# mv-uart.net
KiCad netlist of a schematic drawn in EAGLE
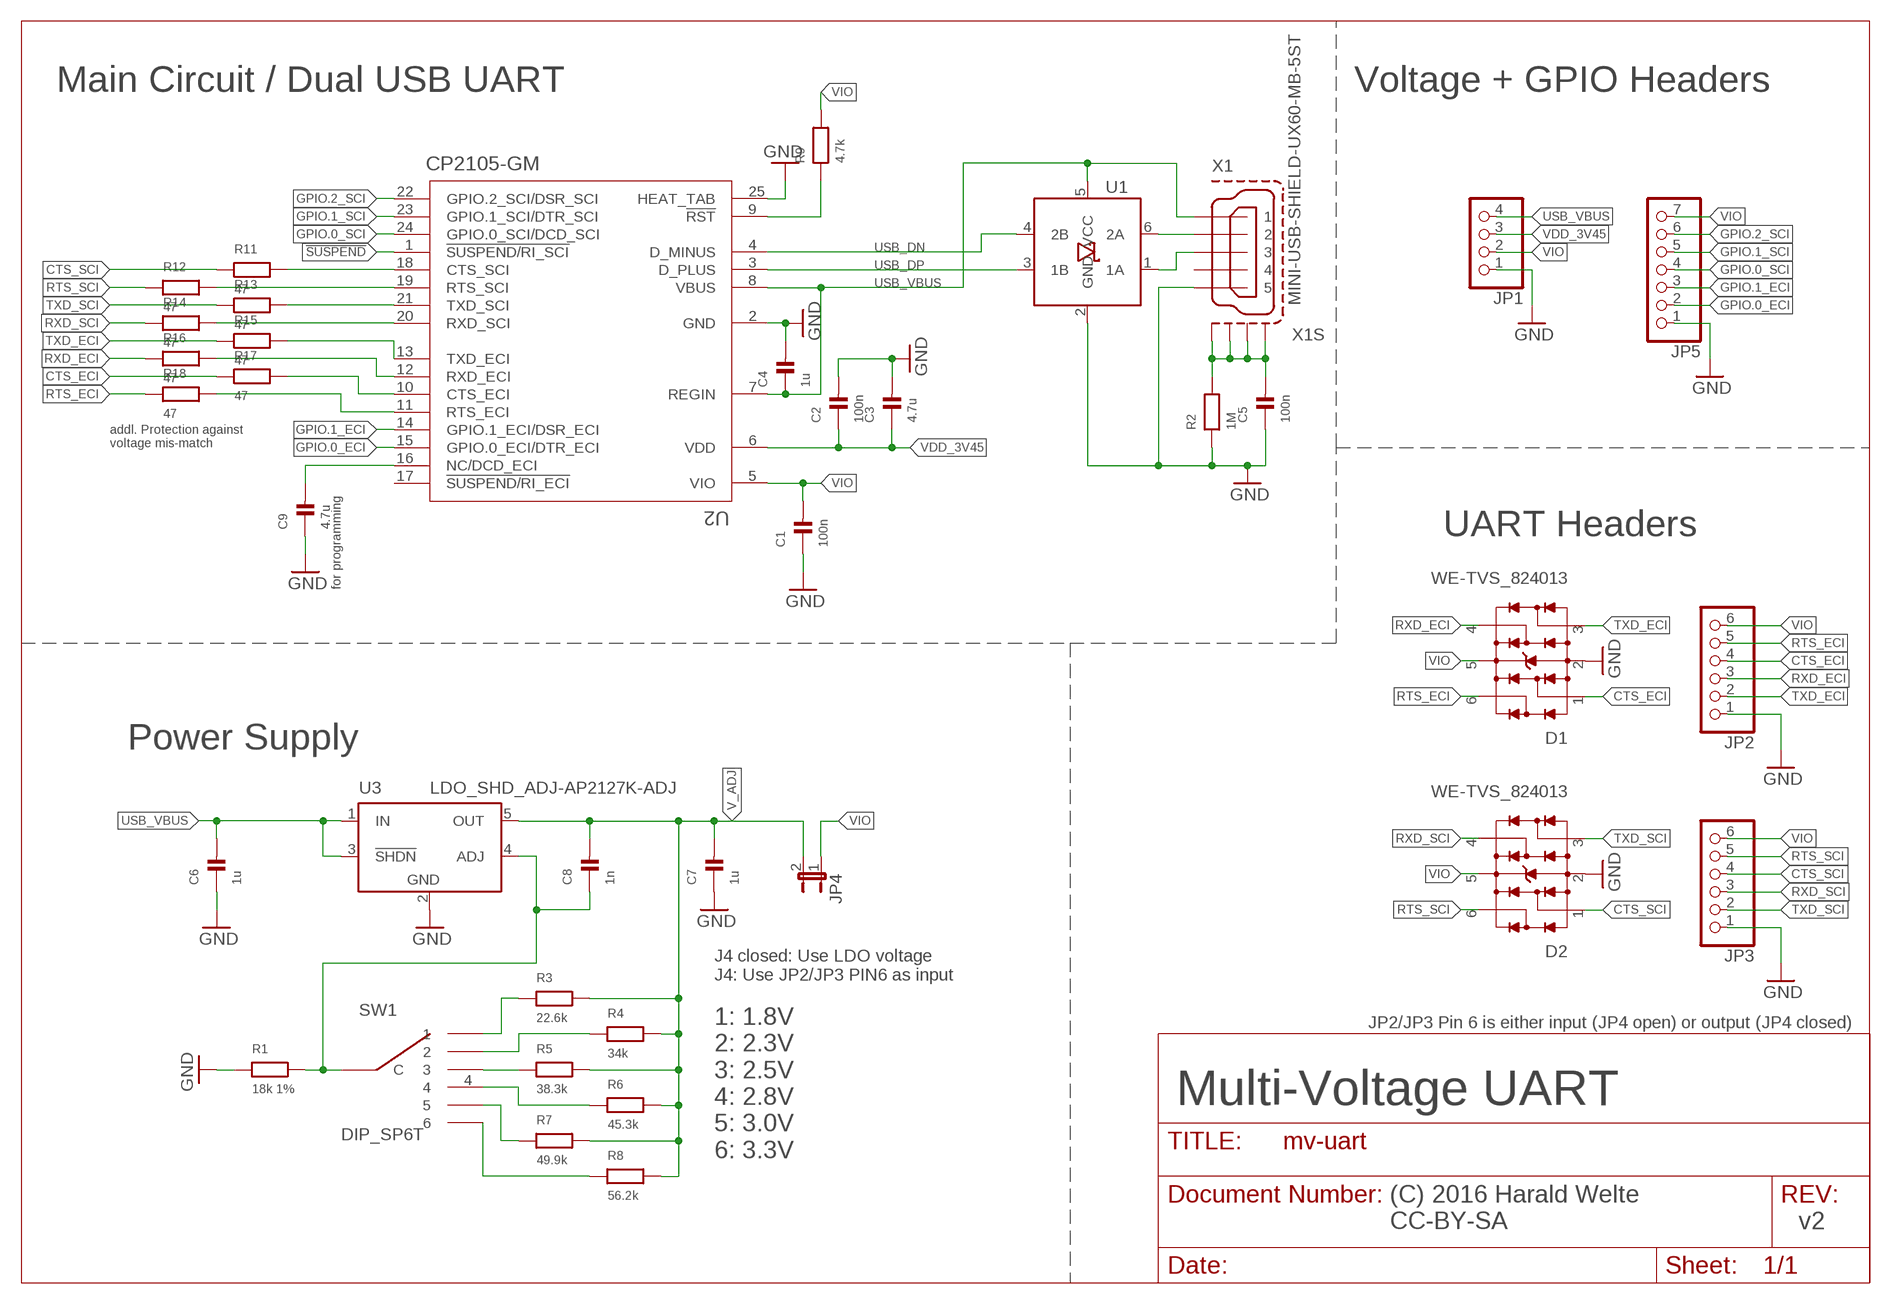
[diagram p0: schematic, sheet 1]

(export (version "E")
  (design (tool "Eeschema 10.0.6"))
  (components
    (comp (ref "C1")
      (value "100n")
      (footprint "eagle-import:_0603")
      (description "0.10µF 16V Ceramic Capacitor X5R 0201 (0603 Metric) 0.024\" L x 0.012\" W (0.60mm x 0.30mm)")
      (fields
        (field (name "MANUFACTURER") "Murata Electronics North America")
        (field (name "MANUFACTURERPARTNUMBER") "GRM033R61C104KE84D")
      )
      (libsource (lib "eagle-import") (part "CAP_CERAMIC_0603"))
    )
    (comp (ref "C2")
      (value "100n")
      (footprint "eagle-import:_0603")
      (description "0.10µF 16V Ceramic Capacitor X5R 0201 (0603 Metric) 0.024\" L x 0.012\" W (0.60mm x 0.30mm)")
      (fields
        (field (name "MANUFACTURER") "Murata Electronics North America")
        (field (name "MANUFACTURERPARTNUMBER") "GRM033R61C104KE84D")
      )
      (libsource (lib "eagle-import") (part "CAP_CERAMIC_0603"))
    )
    (comp (ref "C3")
      (value "4.7u")
      (footprint "eagle-import:_0603")
      (description "4.7µF 10V Ceramic Capacitor X5R 0603 (1608 Metric) 0.063\" L x 0.031\" W (1.60mm x 0.80mm)")
      (fields
        (field (name "MANUFACTURER") "Samsung Electro-Mechanics America, Inc.")
        (field (name "MANUFACTURERPARTNUMBER") "CL10A475KP8NNNC")
      )
      (libsource (lib "eagle-import") (part "CAP_CERAMIC_0603"))
    )
    (comp (ref "C4")
      (value "1u")
      (footprint "eagle-import:_0603")
      (description "1µF 16V Ceramic Capacitor X5R 0603 (1608 Metric) 0.063\" L x 0.031\" W (1.60mm x 0.80mm)")
      (fields
        (field (name "MANUFACTURER") "Murata Electronics North America")
        (field (name "MANUFACTURERPARTNUMBER") "GRM188R61C105KA93J")
      )
      (libsource (lib "eagle-import") (part "CAP_CERAMIC_0603"))
    )
    (comp (ref "C5")
      (value "100n")
      (footprint "eagle-import:_0603")
      (description "0.10µF 16V Ceramic Capacitor X5R 0201 (0603 Metric) 0.024\" L x 0.012\" W (0.60mm x 0.30mm)")
      (fields
        (field (name "MANUFACTURER") "Murata Electronics North America")
        (field (name "MANUFACTURERPARTNUMBER") "GRM033R61C104KE84D")
      )
      (libsource (lib "eagle-import") (part "CAP_CERAMIC_0603"))
    )
    (comp (ref "C6")
      (value "1u")
      (footprint "eagle-import:_0603")
      (description "1µF 16V Ceramic Capacitor X5R 0603 (1608 Metric) 0.063\" L x 0.031\" W (1.60mm x 0.80mm)")
      (fields
        (field (name "MANUFACTURER") "Murata Electronics North America")
        (field (name "MANUFACTURERPARTNUMBER") "GRM188R61C105KA93J")
      )
      (libsource (lib "eagle-import") (part "CAP_CERAMIC_0603"))
    )
    (comp (ref "C7")
      (value "1u")
      (footprint "eagle-import:_0603")
      (description "1µF 16V Ceramic Capacitor X5R 0603 (1608 Metric) 0.063\" L x 0.031\" W (1.60mm x 0.80mm)")
      (fields
        (field (name "MANUFACTURER") "Murata Electronics North America")
        (field (name "MANUFACTURERPARTNUMBER") "GRM188R61C105KA93J")
      )
      (libsource (lib "eagle-import") (part "CAP_CERAMIC_0603"))
    )
    (comp (ref "C8")
      (value "1n")
      (footprint "eagle-import:_0603")
      (description "1000pF 100V Ceramic Capacitor X7R 0603 (1608 Metric) 0.063\" L x 0.031\" W (1.60mm x 0.80mm)")
      (fields
        (field (name "MANUFACTURER") "Samsung Electro-Mechanics America, Inc.")
        (field (name "MANUFACTURERPARTNUMBER") "CL10B102KC8NNNC")
      )
      (libsource (lib "eagle-import") (part "CAP_CERAMIC_0603"))
    )
    (comp (ref "C9")
      (value "4.7u")
      (footprint "eagle-import:_0603")
      (description "4.7µF 10V Ceramic Capacitor X5R 0603 (1608 Metric) 0.063\" L x 0.031\" W (1.60mm x 0.80mm)")
      (fields
        (field (name "MANUFACTURER") "Samsung Electro-Mechanics America, Inc.")
        (field (name "MANUFACTURERPARTNUMBER") "CL10A475KP8NNNC")
      )
      (libsource (lib "eagle-import") (part "CAP_CERAMIC_0603"))
    )
    (comp (ref "D1")
      (value "WE-TVS_824013")
      (footprint "eagle-import:WE-TVS_SOT23-6L")
      (description "TVS DIODE 3.3VWM 6VC SOT23")
      (fields
        (field (name "MANUFACTURER") "Wurth Electronics Inc")
        (field (name "MANUFACTURERPARTNUMBER") "824013")
      )
      (libsource (lib "eagle-import") (part "WE-TVS_824013"))
    )
    (comp (ref "D2")
      (value "WE-TVS_824013")
      (footprint "eagle-import:WE-TVS_SOT23-6L")
      (description "TVS DIODE 3.3VWM 6VC SOT23")
      (fields
        (field (name "MANUFACTURER") "Wurth Electronics Inc")
        (field (name "MANUFACTURERPARTNUMBER") "824013")
      )
      (libsource (lib "eagle-import") (part "WE-TVS_824013"))
    )
    (comp (ref "JP1")
      (value "PINHD-1X4")
      (footprint "eagle-import:1X04")
      (description "4 Positions Header, Unshrouded, Breakaway Connector 0.100\" (2.54mm) Through Hole Gold")
      (fields
        (field (name "MANUFACTURER") "Harwin Inc.")
        (field (name "MANUFACTURERPARTNUMBER") "M20-9990445")
      )
      (libsource (lib "eagle-import") (part "PINHD-1X4"))
    )
    (comp (ref "JP2")
      (value "PINHD-1X6/90")
      (footprint "eagle-import:1X06_90")
      (fields
        (field (name "MANUFACTURER") "Harwin Inc.")
        (field (name "MANUFACTURERPARTNUMBER") "M20-9960645")
      )
      (libsource (lib "eagle-import") (part "PINHD-1X6/90"))
    )
    (comp (ref "JP3")
      (value "PINHD-1X6/90")
      (footprint "eagle-import:1X06_90")
      (fields
        (field (name "MANUFACTURER") "Harwin Inc.")
        (field (name "MANUFACTURERPARTNUMBER") "M20-9960645")
      )
      (libsource (lib "eagle-import") (part "PINHD-1X6/90"))
    )
    (comp (ref "JP4")
      (value "JP1E")
      (footprint "eagle-import:JP1")
      (description "NO DESCRIPTION")
      (fields
        (field (name "MANUFACTURER") "UNKNOWN MANUFACTURER")
        (field (name "MANUFACTURERPARTNUMBER") "UNKNOWN MANUFACTURER PART NUMBER")
      )
      (libsource (lib "eagle-import") (part "JP1E"))
    )
    (comp (ref "JP5")
      (value "PINHD-1X7")
      (footprint "eagle-import:1X07")
      (description "7 Positions Header, Unshrouded, Breakaway Connector 0.100\" (2.54mm) Through Hole Gold")
      (fields
        (field (name "MANUFACTURER") "Sullins Connector Solutions")
        (field (name "MANUFACTURERPARTNUMBER") "PRPC007SAAN-RC")
      )
      (libsource (lib "eagle-import") (part "PINHD-1X7"))
    )
    (comp (ref "R1")
      (value "18k 1%")
      (footprint "eagle-import:_0603")
      (description "RES SMD 18K OHM 1% 1/10W 0603")
      (fields (field (name "MANUFACTURER") "Yageo") (field (name "MANUFACTURERPARTNUMBER") "RC0603FR-0718KL"))
      (libsource (lib "eagle-import") (part "RESISTOR_0603"))
    )
    (comp (ref "R2")
      (value "1M")
      (footprint "eagle-import:_0603")
      (description "RES SMD 1M OHM 5% 1/20W 0201")
      (fields
        (field (name "MANUFACTURER") "Samsung Electro-Mechanics America, Inc.")
        (field (name "MANUFACTURERPARTNUMBER") "RC0603J105CS")
      )
      (libsource (lib "eagle-import") (part "RESISTOR_0603"))
    )
    (comp (ref "R3")
      (value "22.6k")
      (footprint "eagle-import:_0603")
      (description "RES SMD 22.6K OHM 1% 1/10W 0603")
      (fields
        (field (name "MANUFACTURER") "Yageo")
        (field (name "MANUFACTURERPARTNUMBER") "RC0603FR-0722K6L")
      )
      (libsource (lib "eagle-import") (part "RESISTOR_0603"))
    )
    (comp (ref "R4")
      (value "34k")
      (footprint "eagle-import:_0603")
      (description "RES SMD 34K OHM 1% 1/10W 0603")
      (fields (field (name "MANUFACTURER") "Yageo") (field (name "MANUFACTURERPARTNUMBER") "RC0603FR-0734KL"))
      (libsource (lib "eagle-import") (part "RESISTOR_0603"))
    )
    (comp (ref "R5")
      (value "38.3k")
      (footprint "eagle-import:_0603")
      (description "RES SMD 38.3K OHM 1% 1/10W 0603")
      (fields
        (field (name "MANUFACTURER") "Yageo")
        (field (name "MANUFACTURERPARTNUMBER") "RC0603FR-0738K3L")
      )
      (libsource (lib "eagle-import") (part "RESISTOR_0603"))
    )
    (comp (ref "R6")
      (value "45.3k")
      (footprint "eagle-import:_0603")
      (description "RES SMD 45.3K OHM 1% 1/10W 0603")
      (fields
        (field (name "MANUFACTURER") "Yageo")
        (field (name "MANUFACTURERPARTNUMBER") "RC0603FR-0745K3L")
      )
      (libsource (lib "eagle-import") (part "RESISTOR_0603"))
    )
    (comp (ref "R7")
      (value "49.9k")
      (footprint "eagle-import:_0603")
      (description "RES SMD 49.9K OHM 1% 1/10W 0603")
      (fields
        (field (name "MANUFACTURER") "Yageo")
        (field (name "MANUFACTURERPARTNUMBER") "RC0603FR-0749K9L")
      )
      (libsource (lib "eagle-import") (part "RESISTOR_0603"))
    )
    (comp (ref "R8")
      (value "56.2k")
      (footprint "eagle-import:_0603")
      (description "RES SMD 56.2K OHM 1% 1/10W 0603")
      (fields
        (field (name "MANUFACTURER") "Yageo")
        (field (name "MANUFACTURERPARTNUMBER") "RC0603FR-0756K2L")
      )
      (libsource (lib "eagle-import") (part "RESISTOR_0603"))
    )
    (comp (ref "R9")
      (value "4.7k")
      (footprint "eagle-import:_0603")
      (description "RES SMD 4.7K OHM 5% 1/10W 0603")
      (fields (field (name "MANUFACTURER") "Yageo") (field (name "MANUFACTURERPARTNUMBER") "RC0603JR-074K7L"))
      (libsource (lib "eagle-import") (part "RESISTOR_0603"))
    )
    (comp (ref "R11")
      (value "47")
      (footprint "eagle-import:_0603")
      (description "RES SMD 47 OHM 5% 1/10W 0603")
      (fields (field (name "MANUFACTURER") "Yageo") (field (name "MANUFACTURERPARTNUMBER") "RC0603JR-0747RL"))
      (libsource (lib "eagle-import") (part "RESISTOR_0603"))
    )
    (comp (ref "R12")
      (value "47")
      (footprint "eagle-import:_0603")
      (description "RES SMD 47 OHM 5% 1/10W 0603")
      (fields (field (name "MANUFACTURER") "Yageo") (field (name "MANUFACTURERPARTNUMBER") "RC0603JR-0747RL"))
      (libsource (lib "eagle-import") (part "RESISTOR_0603"))
    )
    (comp (ref "R13")
      (value "47")
      (footprint "eagle-import:_0603")
      (description "RES SMD 47 OHM 5% 1/10W 0603")
      (fields (field (name "MANUFACTURER") "Yageo") (field (name "MANUFACTURERPARTNUMBER") "RC0603JR-0747RL"))
      (libsource (lib "eagle-import") (part "RESISTOR_0603"))
    )
    (comp (ref "R14")
      (value "47")
      (footprint "eagle-import:_0603")
      (description "RES SMD 47 OHM 5% 1/10W 0603")
      (fields (field (name "MANUFACTURER") "Yageo") (field (name "MANUFACTURERPARTNUMBER") "RC0603JR-0747RL"))
      (libsource (lib "eagle-import") (part "RESISTOR_0603"))
    )
    (comp (ref "R15")
      (value "47")
      (footprint "eagle-import:_0603")
      (description "RES SMD 47 OHM 5% 1/10W 0603")
      (fields (field (name "MANUFACTURER") "Yageo") (field (name "MANUFACTURERPARTNUMBER") "RC0603JR-0747RL"))
      (libsource (lib "eagle-import") (part "RESISTOR_0603"))
    )
    (comp (ref "R16")
      (value "47")
      (footprint "eagle-import:_0603")
      (description "RES SMD 47 OHM 5% 1/10W 0603")
      (fields (field (name "MANUFACTURER") "Yageo") (field (name "MANUFACTURERPARTNUMBER") "RC0603JR-0747RL"))
      (libsource (lib "eagle-import") (part "RESISTOR_0603"))
    )
    (comp (ref "R17")
      (value "47")
      (footprint "eagle-import:_0603")
      (description "RES SMD 47 OHM 5% 1/10W 0603")
      (fields (field (name "MANUFACTURER") "Yageo") (field (name "MANUFACTURERPARTNUMBER") "RC0603JR-0747RL"))
      (libsource (lib "eagle-import") (part "RESISTOR_0603"))
    )
    (comp (ref "R18")
      (value "47")
      (footprint "eagle-import:_0603")
      (description "RES SMD 47 OHM 5% 1/10W 0603")
      (fields (field (name "MANUFACTURER") "Yageo") (field (name "MANUFACTURERPARTNUMBER") "RC0603JR-0747RL"))
      (libsource (lib "eagle-import") (part "RESISTOR_0603"))
    )
    (comp (ref "SW1")
      (value "DIP_SP6T")
      (footprint "eagle-import:DIP_SP6T")
      (description "Dip Switch SP6T 6 Position Through Hole Rotary with Shaft Actuator 100mA 5VDC")
      (fields
        (field (name "MANUFACTURER") "Copal Electronics Inc.")
        (field (name "MANUFACTURERPARTNUMBER") "SS-10-16SP-L-AE")
      )
      (libsource (lib "eagle-import") (part "DIP_SP6T"))
    )
    (comp (ref "U1")
      (value "IP4234CZ6")
      (footprint "eagle-import:TSOP-6")
      (description "TVS DIODE 5.5VWM 6TSOP")
      (fields
        (field (name "MANUFACTURER") "NXP Semiconductors")
        (field (name "MANUFACTURERPARTNUMBER") "IP4234CZ6,125")
      )
      (libsource (lib "eagle-import") (part "IP4234CZ6"))
    )
    (comp (ref "U2")
      (value "CP2105-GM")
      (footprint "eagle-import:QFN24_4X4")
      (description "USB Bridge, USB to UART USB 2.0 UART Interface 24-QFN (4x4)")
      (fields
        (field (name "MANUFACTURER") "Silicon Labs")
        (field (name "MANUFACTURERPARTNUMBER") "CP2105-F01-GM")
      )
      (libsource (lib "eagle-import") (part "CP2105-GM"))
    )
    (comp (ref "U3")
      (value "LDO_SHD_ADJ-AP2127K-ADJ")
      (footprint "eagle-import:SOT23L")
      (description "Linear Voltage Regulator IC Positive Adjustable 1 Output 0.8 V ~ 5.5 V 300mA SOT-23-5")
      (fields
        (field (name "MANUFACTURER") "Diodes Incorporated")
        (field (name "MANUFACTURERPARTNUMBER") "AP2127K-ADJTRG1")
      )
      (libsource (lib "eagle-import") (part "LDO_SHD_ADJ-AP2127K-ADJ"))
    )
    (comp (ref "X1")
      (value "MINI-USB-SHIELD-UX60-MB-5ST")
      (footprint "eagle-import:UX60-MB-5ST")
      (description "USB - mini B USB 2.0 Receptacle Connector 5 Position Surface Mount, Right Angle, Horizontal")
      (fields
        (field (name "MANUFACTURER") "Hirose Electric Co Ltd")
        (field (name "MANUFACTURERPARTNUMBER") "UX60-MB-5ST")
        (field (name "CLASS") "CONNECTOR")
        (field (name "LINK") "http://www.digikey.com/product-detail/en/hirose-electric-co-ltd/UX60-MB-5ST/H2959CT-ND/597538")
        (field (name "POPULATED") "TRUE")
        (field (name "ROHSCERTIFICATE") "UNKNOWN ROHS CERTIFICATE")
        (field (name "SOURCE") "DIGIKEY")
        (field (name "SOURCEPARTNUMBER") "H2959CT-ND")
      )
      (libsource (lib "eagle-import") (part "MINI-USB-SHIELD-UX60-MB-5ST"))
    )
  )
  (nets
    (net (code "1") (name "/USB_DN") (class "Default")
      (node (ref "U1") (pin "4") (pinfunction "2B_4") (pintype "passive"))
      (node (ref "U2") (pin "4") (pinfunction "D_MINUS_4") (pintype "passive"))
    )
    (net (code "2") (name "/USB_DP") (class "Default")
      (node (ref "U1") (pin "3") (pinfunction "1B_3") (pintype "passive"))
      (node (ref "U2") (pin "3") (pinfunction "D_PLUS_3") (pintype "passive"))
    )
    (net (code "3") (name "/~{SUSPEND}") (class "Default")
      (node (ref "U2") (pin "1") (pinfunction "~{SUSPEND/RI_SCI}_1") (pintype "passive"))
    )
    (net (code "4") (name "CTS_ECI") (class "Default")
      (node (ref "D1") (pin "1") (pinfunction "1_1") (pintype "passive"))
      (node (ref "JP2") (pin "4") (pinfunction "4_4") (pintype "passive"))
      (node (ref "R17") (pin "1") (pinfunction "1_1") (pintype "passive"))
    )
    (net (code "5") (name "CTS_SCI") (class "Default")
      (node (ref "D2") (pin "1") (pinfunction "1_1") (pintype "passive"))
      (node (ref "JP3") (pin "4") (pinfunction "4_4") (pintype "passive"))
      (node (ref "R11") (pin "1") (pinfunction "1_1") (pintype "passive"))
    )
    (net (code "6") (name "GND") (class "Default")
      (node (ref "C1") (pin "1") (pinfunction "1_1") (pintype "passive"))
      (node (ref "C2") (pin "2") (pinfunction "2_2") (pintype "passive"))
      (node (ref "C3") (pin "2") (pinfunction "2_2") (pintype "passive"))
      (node (ref "C4") (pin "2") (pinfunction "2_2") (pintype "passive"))
      (node (ref "C5") (pin "1") (pinfunction "1_1") (pintype "passive"))
      (node (ref "C6") (pin "1") (pinfunction "1_1") (pintype "passive"))
      (node (ref "C7") (pin "1") (pinfunction "1_1") (pintype "passive"))
      (node (ref "C9") (pin "1") (pinfunction "1_1") (pintype "passive"))
      (node (ref "D1") (pin "2") (pinfunction "GND_2") (pintype "power_in"))
      (node (ref "D2") (pin "2") (pinfunction "GND_2") (pintype "power_in"))
      (node (ref "JP1") (pin "1") (pinfunction "1_1") (pintype "passive"))
      (node (ref "JP2") (pin "1") (pinfunction "1_1") (pintype "passive"))
      (node (ref "JP3") (pin "1") (pinfunction "1_1") (pintype "passive"))
      (node (ref "JP5") (pin "1") (pinfunction "1_1") (pintype "passive"))
      (node (ref "R1") (pin "1") (pinfunction "1_1") (pintype "passive"))
      (node (ref "R2") (pin "1") (pinfunction "1_1") (pintype "passive"))
      (node (ref "U1") (pin "2") (pinfunction "GND_2") (pintype "passive"))
      (node (ref "U2") (pin "2") (pinfunction "GND_2") (pintype "power_in"))
      (node (ref "U2") (pin "25") (pinfunction "HEAT_TAB_25") (pintype "passive"))
      (node (ref "U3") (pin "2") (pinfunction "GND_2") (pintype "power_in"))
      (node (ref "X1") (pin "5") (pinfunction "5_5") (pintype "input"))
    )
    (net (code "7") (name "GPIO.0_ECI") (class "Default")
      (node (ref "JP5") (pin "2") (pinfunction "2_2") (pintype "passive"))
      (node (ref "U2") (pin "15") (pinfunction "GPIO.0_ECI/DTR_ECI_15") (pintype "passive"))
    )
    (net (code "8") (name "GPIO.0_SCI") (class "Default")
      (node (ref "JP5") (pin "4") (pinfunction "4_4") (pintype "passive"))
      (node (ref "U2") (pin "24") (pinfunction "GPIO.0_SCI/DCD_SCI_24") (pintype "passive"))
    )
    (net (code "9") (name "GPIO.1_ECI") (class "Default")
      (node (ref "JP5") (pin "3") (pinfunction "3_3") (pintype "passive"))
      (node (ref "U2") (pin "14") (pinfunction "GPIO.1_ECI/DSR_ECI_14") (pintype "passive"))
    )
    (net (code "10") (name "GPIO.1_SCI") (class "Default")
      (node (ref "JP5") (pin "5") (pinfunction "5_5") (pintype "passive"))
      (node (ref "U2") (pin "23") (pinfunction "GPIO.1_SCI/DTR_SCI_23") (pintype "passive"))
    )
    (net (code "11") (name "GPIO.2_SCI") (class "Default")
      (node (ref "JP5") (pin "6") (pinfunction "6_6") (pintype "passive"))
      (node (ref "U2") (pin "22") (pinfunction "GPIO.2_SCI/DSR_SCI_22") (pintype "passive"))
    )
    (net (code "12") (name "Net-(R3-Pad1)") (class "Default")
      (node (ref "R3") (pin "1") (pinfunction "1_1") (pintype "passive"))
      (node (ref "SW1") (pin "1") (pinfunction "1_1") (pintype "bidirectional"))
    )
    (net (code "13") (name "Net-(R4-Pad1)") (class "Default")
      (node (ref "R4") (pin "1") (pinfunction "1_1") (pintype "passive"))
      (node (ref "SW1") (pin "2") (pinfunction "2_2") (pintype "bidirectional"))
    )
    (net (code "14") (name "Net-(R5-Pad1)") (class "Default")
      (node (ref "R5") (pin "1") (pinfunction "1_1") (pintype "passive"))
      (node (ref "SW1") (pin "3") (pinfunction "3_3") (pintype "bidirectional"))
    )
    (net (code "15") (name "Net-(R6-Pad1)") (class "Default")
      (node (ref "R6") (pin "1") (pinfunction "1_1") (pintype "passive"))
      (node (ref "SW1") (pin "4") (pinfunction "4_4") (pintype "bidirectional"))
    )
    (net (code "16") (name "Net-(R7-Pad1)") (class "Default")
      (node (ref "R7") (pin "1") (pinfunction "1_1") (pintype "passive"))
      (node (ref "SW1") (pin "5") (pinfunction "5_5") (pintype "bidirectional"))
    )
    (net (code "17") (name "Net-(R8-Pad1)") (class "Default")
      (node (ref "R8") (pin "1") (pinfunction "1_1") (pintype "passive"))
      (node (ref "SW1") (pin "6") (pinfunction "6_6") (pintype "bidirectional"))
    )
    (net (code "18") (name "Net-(U1-1A)") (class "Default")
      (node (ref "U1") (pin "1") (pinfunction "1A_1") (pintype "passive"))
      (node (ref "X1") (pin "3") (pinfunction "3_3") (pintype "input"))
    )
    (net (code "19") (name "Net-(U1-2A)") (class "Default")
      (node (ref "U1") (pin "6") (pinfunction "2A_6") (pintype "passive"))
      (node (ref "X1") (pin "2") (pinfunction "2_2") (pintype "input"))
    )
    (net (code "20") (name "Net-(U2-CTS_ECI)") (class "Default")
      (node (ref "R17") (pin "2") (pinfunction "2_2") (pintype "passive"))
      (node (ref "U2") (pin "10") (pinfunction "CTS_ECI_10") (pintype "passive"))
    )
    (net (code "21") (name "Net-(U2-CTS_SCI)") (class "Default")
      (node (ref "R11") (pin "2") (pinfunction "2_2") (pintype "passive"))
      (node (ref "U2") (pin "18") (pinfunction "CTS_SCI_18") (pintype "passive"))
    )
    (net (code "22") (name "Net-(U2-NC{slash}DCD_ECI)") (class "Default")
      (node (ref "C9") (pin "2") (pinfunction "2_2") (pintype "passive"))
      (node (ref "U2") (pin "16") (pinfunction "NC/DCD_ECI_16") (pintype "passive"))
    )
    (net (code "23") (name "Net-(U2-RTS_ECI)") (class "Default")
      (node (ref "R18") (pin "2") (pinfunction "2_2") (pintype "passive"))
      (node (ref "U2") (pin "11") (pinfunction "RTS_ECI_11") (pintype "passive"))
    )
    (net (code "24") (name "Net-(U2-RTS_SCI)") (class "Default")
      (node (ref "R12") (pin "2") (pinfunction "2_2") (pintype "passive"))
      (node (ref "U2") (pin "19") (pinfunction "RTS_SCI_19") (pintype "passive"))
    )
    (net (code "25") (name "Net-(U2-RXD_ECI)") (class "Default")
      (node (ref "R16") (pin "2") (pinfunction "2_2") (pintype "passive"))
      (node (ref "U2") (pin "12") (pinfunction "RXD_ECI_12") (pintype "passive"))
    )
    (net (code "26") (name "Net-(U2-RXD_SCI)") (class "Default")
      (node (ref "R14") (pin "2") (pinfunction "2_2") (pintype "passive"))
      (node (ref "U2") (pin "20") (pinfunction "RXD_SCI_20") (pintype "passive"))
    )
    (net (code "27") (name "Net-(U2-TXD_ECI)") (class "Default")
      (node (ref "R15") (pin "2") (pinfunction "2_2") (pintype "passive"))
      (node (ref "U2") (pin "13") (pinfunction "TXD_ECI_13") (pintype "passive"))
    )
    (net (code "28") (name "Net-(U2-TXD_SCI)") (class "Default")
      (node (ref "R13") (pin "2") (pinfunction "2_2") (pintype "passive"))
      (node (ref "U2") (pin "21") (pinfunction "TXD_SCI_21") (pintype "passive"))
    )
    (net (code "29") (name "Net-(U2-~{RST})") (class "Default")
      (node (ref "R9") (pin "1") (pinfunction "1_1") (pintype "passive"))
      (node (ref "U2") (pin "9") (pinfunction "~{RST}_9") (pintype "passive"))
    )
    (net (code "30") (name "Net-(U3-ADJ)") (class "Default")
      (node (ref "C8") (pin "1") (pinfunction "1_1") (pintype "passive"))
      (node (ref "R1") (pin "2") (pinfunction "2_2") (pintype "passive"))
      (node (ref "SW1") (pin "C") (pinfunction "C_C") (pintype "bidirectional"))
      (node (ref "U3") (pin "4") (pinfunction "ADJ_4") (pintype "passive"))
    )
    (net (code "31") (name "Net-(X1B-S1)") (class "Default")
      (node (ref "C5") (pin "2") (pinfunction "2_2") (pintype "passive"))
      (node (ref "R2") (pin "2") (pinfunction "2_2") (pintype "passive"))
      (node (ref "X1") (pin "M1") (pinfunction "S1_M1") (pintype "passive"))
      (node (ref "X1") (pin "M2") (pinfunction "S2_M2") (pintype "passive"))
      (node (ref "X1") (pin "M3") (pinfunction "S3_M3") (pintype "passive"))
      (node (ref "X1") (pin "M4") (pinfunction "S4_M4") (pintype "passive"))
    )
    (net (code "32") (name "RTS_ECI") (class "Default")
      (node (ref "D1") (pin "6") (pinfunction "4_6") (pintype "passive"))
      (node (ref "JP2") (pin "5") (pinfunction "5_5") (pintype "passive"))
      (node (ref "R18") (pin "1") (pinfunction "1_1") (pintype "passive"))
    )
    (net (code "33") (name "RTS_SCI") (class "Default")
      (node (ref "D2") (pin "6") (pinfunction "4_6") (pintype "passive"))
      (node (ref "JP3") (pin "5") (pinfunction "5_5") (pintype "passive"))
      (node (ref "R12") (pin "1") (pinfunction "1_1") (pintype "passive"))
    )
    (net (code "34") (name "RXD_ECI") (class "Default")
      (node (ref "D1") (pin "4") (pinfunction "3_4") (pintype "passive"))
      (node (ref "JP2") (pin "3") (pinfunction "3_3") (pintype "passive"))
      (node (ref "R16") (pin "1") (pinfunction "1_1") (pintype "passive"))
    )
    (net (code "35") (name "RXD_SCI") (class "Default")
      (node (ref "D2") (pin "4") (pinfunction "3_4") (pintype "passive"))
      (node (ref "JP3") (pin "3") (pinfunction "3_3") (pintype "passive"))
      (node (ref "R14") (pin "1") (pinfunction "1_1") (pintype "passive"))
    )
    (net (code "36") (name "TXD_ECI") (class "Default")
      (node (ref "D1") (pin "3") (pinfunction "2_3") (pintype "passive"))
      (node (ref "JP2") (pin "2") (pinfunction "2_2") (pintype "passive"))
      (node (ref "R15") (pin "1") (pinfunction "1_1") (pintype "passive"))
    )
    (net (code "37") (name "TXD_SCI") (class "Default")
      (node (ref "D2") (pin "3") (pinfunction "2_3") (pintype "passive"))
      (node (ref "JP3") (pin "2") (pinfunction "2_2") (pintype "passive"))
      (node (ref "R13") (pin "1") (pinfunction "1_1") (pintype "passive"))
    )
    (net (code "38") (name "USB_VBUS") (class "Default")
      (node (ref "C4") (pin "1") (pinfunction "1_1") (pintype "passive"))
      (node (ref "C6") (pin "2") (pinfunction "2_2") (pintype "passive"))
      (node (ref "JP1") (pin "4") (pinfunction "4_4") (pintype "passive"))
      (node (ref "U1") (pin "5") (pinfunction "VCC_5") (pintype "passive"))
      (node (ref "U2") (pin "7") (pinfunction "REGIN_7") (pintype "input"))
      (node (ref "U2") (pin "8") (pinfunction "VBUS_8") (pintype "input"))
      (node (ref "U3") (pin "1") (pinfunction "IN_1") (pintype "input"))
      (node (ref "U3") (pin "3") (pinfunction "~{SHDN}_3") (pintype "input"))
      (node (ref "X1") (pin "1") (pinfunction "1_1") (pintype "input"))
    )
    (net (code "39") (name "VDD_3V45") (class "Default")
      (node (ref "C2") (pin "1") (pinfunction "1_1") (pintype "passive"))
      (node (ref "C3") (pin "1") (pinfunction "1_1") (pintype "passive"))
      (node (ref "JP1") (pin "3") (pinfunction "3_3") (pintype "passive"))
      (node (ref "U2") (pin "6") (pinfunction "VDD_6") (pintype "power_in"))
    )
    (net (code "40") (name "VIO") (class "Default")
      (node (ref "C1") (pin "2") (pinfunction "2_2") (pintype "passive"))
      (node (ref "D1") (pin "5") (pinfunction "VDD_5") (pintype "power_in"))
      (node (ref "D2") (pin "5") (pinfunction "VDD_5") (pintype "power_in"))
      (node (ref "JP1") (pin "2") (pinfunction "2_2") (pintype "passive"))
      (node (ref "JP2") (pin "6") (pinfunction "6_6") (pintype "passive"))
      (node (ref "JP3") (pin "6") (pinfunction "6_6") (pintype "passive"))
      (node (ref "JP4") (pin "1") (pinfunction "1_1") (pintype "passive"))
      (node (ref "JP5") (pin "7") (pinfunction "7_7") (pintype "passive"))
      (node (ref "R9") (pin "2") (pinfunction "2_2") (pintype "passive"))
      (node (ref "U2") (pin "5") (pinfunction "VIO_5") (pintype "power_in"))
    )
    (net (code "41") (name "V_ADJ") (class "Default")
      (node (ref "C7") (pin "2") (pinfunction "2_2") (pintype "passive"))
      (node (ref "C8") (pin "2") (pinfunction "2_2") (pintype "passive"))
      (node (ref "JP4") (pin "2") (pinfunction "2_2") (pintype "passive"))
      (node (ref "R3") (pin "2") (pinfunction "2_2") (pintype "passive"))
      (node (ref "R4") (pin "2") (pinfunction "2_2") (pintype "passive"))
      (node (ref "R5") (pin "2") (pinfunction "2_2") (pintype "passive"))
      (node (ref "R6") (pin "2") (pinfunction "2_2") (pintype "passive"))
      (node (ref "R7") (pin "2") (pinfunction "2_2") (pintype "passive"))
      (node (ref "R8") (pin "2") (pinfunction "2_2") (pintype "passive"))
      (node (ref "U3") (pin "5") (pinfunction "OUT_5") (pintype "passive"))
    )
    (net (code "42") (name "unconnected-(U2-~{SUSPEND{slash}RI_ECI}-Pad17)") (class "Default")
      (node (ref "U2") (pin "17") (pinfunction "~{SUSPEND/RI_ECI}_17") (pintype "passive"))
    )
    (net (code "43") (name "unconnected-(X1-Pad4)") (class "Default")
      (node (ref "X1") (pin "4") (pinfunction "4_4") (pintype "input"))
    )
  )
)
